# untitled.net
KiCad netlist of a schematic drawn in EAGLE
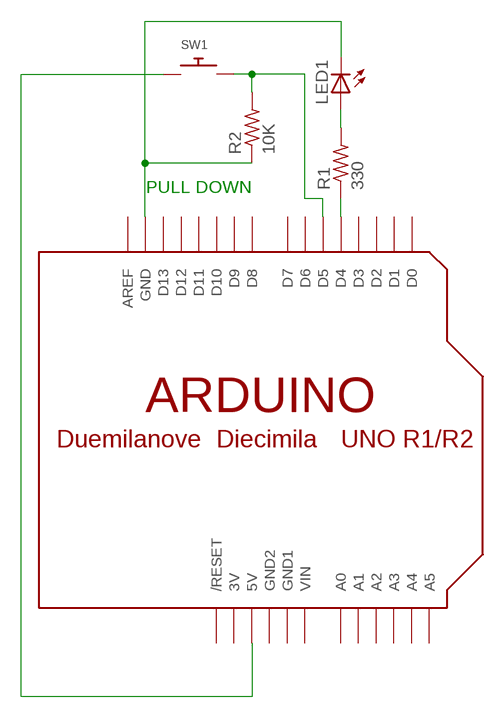
[diagram p0: schematic, sheet 1]

(export (version "E")
  (design (tool "Eeschema 10.0.6"))
  (components
    (comp (ref "LED1")
      (value "LED3MM")
      (footprint "eagle-import:LED3MM")
      (libsource (lib "eagle-import") (part "LED3MM"))
    )
    (comp (ref "R1")
      (value "330")
      (footprint "eagle-import:0204_5")
      (libsource (lib "eagle-import") (part "R-US_0204/5"))
    )
    (comp (ref "R2")
      (value "10K")
      (footprint "eagle-import:0204_5")
      (libsource (lib "eagle-import") (part "R-US_0204/5"))
    )
    (comp (ref "SW1")
      (value "SWITCH_PUSHBUTTONEVQ-PE")
      (footprint "eagle-import:TACT_PANA-EVQ")
      (libsource (lib "eagle-import") (part "SWITCH_PUSHBUTTONEVQ-PE"))
    )
    (comp (ref "U$1")
      (value "ARDUINOUNO")
      (footprint "eagle-import:ARDUINO")
      (libsource (lib "eagle-import") (part "ARDUINOUNO"))
    )
  )
  (nets
    (net (code "1") (name "/3V") (class "Default")
      (node (ref "U$1") (pin "3V") (pinfunction "3V_3V") (pintype "power_in"))
    )
    (net (code "2") (name "/GND1") (class "Default")
      (node (ref "U$1") (pin "GND1") (pinfunction "GND1_GND1") (pintype "power_in"))
    )
    (net (code "3") (name "/GND2") (class "Default")
      (node (ref "U$1") (pin "GND2") (pinfunction "GND2_GND2") (pintype "power_in"))
    )
    (net (code "4") (name "/VIN") (class "Default")
      (node (ref "U$1") (pin "VIN") (pinfunction "VIN_VIN") (pintype "power_in"))
    )
    (net (code "5") (name "Net-(LED1-C)") (class "Default")
      (node (ref "LED1") (pin "K") (pinfunction "C_K") (pintype "passive"))
      (node (ref "R2") (pin "1") (pinfunction "1_1") (pintype "passive"))
      (node (ref "U$1") (pin "GND") (pinfunction "GND_GND") (pintype "power_in"))
    )
    (net (code "6") (name "Net-(LED1-PadA)") (class "Default")
      (node (ref "LED1") (pin "A") (pinfunction "A_A") (pintype "passive"))
      (node (ref "R1") (pin "2") (pinfunction "2_2") (pintype "passive"))
    )
    (net (code "7") (name "Net-(R1-Pad1)") (class "Default")
      (node (ref "R1") (pin "1") (pinfunction "1_1") (pintype "passive"))
      (node (ref "U$1") (pin "D4") (pinfunction "D4_D4") (pintype "bidirectional"))
    )
    (net (code "8") (name "Net-(R2-Pad2)") (class "Default")
      (node (ref "R2") (pin "2") (pinfunction "2_2") (pintype "passive"))
      (node (ref "SW1") (pin "P$2") (pinfunction "P$2_P$2") (pintype "passive"))
      (node (ref "U$1") (pin "D5") (pinfunction "D5_D5") (pintype "bidirectional"))
    )
    (net (code "9") (name "Net-(SW1-PadP$1)") (class "Default")
      (node (ref "SW1") (pin "P$1") (pinfunction "P$1_P$1") (pintype "passive"))
      (node (ref "U$1") (pin "5V") (pinfunction "5V_5V") (pintype "power_in"))
    )
    (net (code "10") (name "unconnected-(U$1-PadA0)") (class "Default")
      (node (ref "U$1") (pin "A0") (pinfunction "A0_A0") (pintype "bidirectional"))
    )
    (net (code "11") (name "unconnected-(U$1-PadA1)") (class "Default")
      (node (ref "U$1") (pin "A1") (pinfunction "A1_A1") (pintype "bidirectional"))
    )
    (net (code "12") (name "unconnected-(U$1-PadA2)") (class "Default")
      (node (ref "U$1") (pin "A2") (pinfunction "A2_A2") (pintype "bidirectional"))
    )
    (net (code "13") (name "unconnected-(U$1-PadA3)") (class "Default")
      (node (ref "U$1") (pin "A3") (pinfunction "A3_A3") (pintype "bidirectional"))
    )
    (net (code "14") (name "unconnected-(U$1-PadA4)") (class "Default")
      (node (ref "U$1") (pin "A4") (pinfunction "A4_A4") (pintype "bidirectional"))
    )
    (net (code "15") (name "unconnected-(U$1-PadA5)") (class "Default")
      (node (ref "U$1") (pin "A5") (pinfunction "A5_A5") (pintype "bidirectional"))
    )
    (net (code "16") (name "unconnected-(U$1-PadAREF)") (class "Default")
      (node (ref "U$1") (pin "AREF") (pinfunction "AREF_AREF") (pintype "bidirectional"))
    )
    (net (code "17") (name "unconnected-(U$1-PadD0)") (class "Default")
      (node (ref "U$1") (pin "D0") (pinfunction "D0_D0") (pintype "bidirectional"))
    )
    (net (code "18") (name "unconnected-(U$1-PadD1)") (class "Default")
      (node (ref "U$1") (pin "D1") (pinfunction "D1_D1") (pintype "bidirectional"))
    )
    (net (code "19") (name "unconnected-(U$1-PadD2)") (class "Default")
      (node (ref "U$1") (pin "D2") (pinfunction "D2_D2") (pintype "bidirectional"))
    )
    (net (code "20") (name "unconnected-(U$1-PadD3)") (class "Default")
      (node (ref "U$1") (pin "D3") (pinfunction "D3_D3") (pintype "bidirectional"))
    )
    (net (code "21") (name "unconnected-(U$1-PadD6)") (class "Default")
      (node (ref "U$1") (pin "D6") (pinfunction "D6_D6") (pintype "bidirectional"))
    )
    (net (code "22") (name "unconnected-(U$1-PadD7)") (class "Default")
      (node (ref "U$1") (pin "D7") (pinfunction "D7_D7") (pintype "bidirectional"))
    )
    (net (code "23") (name "unconnected-(U$1-PadD8)") (class "Default")
      (node (ref "U$1") (pin "D8") (pinfunction "D8_D8") (pintype "bidirectional"))
    )
    (net (code "24") (name "unconnected-(U$1-PadD9)") (class "Default")
      (node (ref "U$1") (pin "D9") (pinfunction "D9_D9") (pintype "bidirectional"))
    )
    (net (code "25") (name "unconnected-(U$1-PadD10)") (class "Default")
      (node (ref "U$1") (pin "D10") (pinfunction "D10_D10") (pintype "bidirectional"))
    )
    (net (code "26") (name "unconnected-(U$1-PadD11)") (class "Default")
      (node (ref "U$1") (pin "D11") (pinfunction "D11_D11") (pintype "bidirectional"))
    )
    (net (code "27") (name "unconnected-(U$1-PadD12)") (class "Default")
      (node (ref "U$1") (pin "D12") (pinfunction "D12_D12") (pintype "bidirectional"))
    )
    (net (code "28") (name "unconnected-(U$1-PadD13)") (class "Default")
      (node (ref "U$1") (pin "D13") (pinfunction "D13_D13") (pintype "bidirectional"))
    )
    (net (code "29") (name "unconnected-(U$1-{slash}RESET-PadRESET)") (class "Default")
      (node (ref "U$1") (pin "RESET") (pinfunction "/RESET_RESET") (pintype "bidirectional"))
    )
  )
)
